# PAGE2-SFP_CONNECTORS.net
KiCad netlist of a schematic drawn in Altium Designer
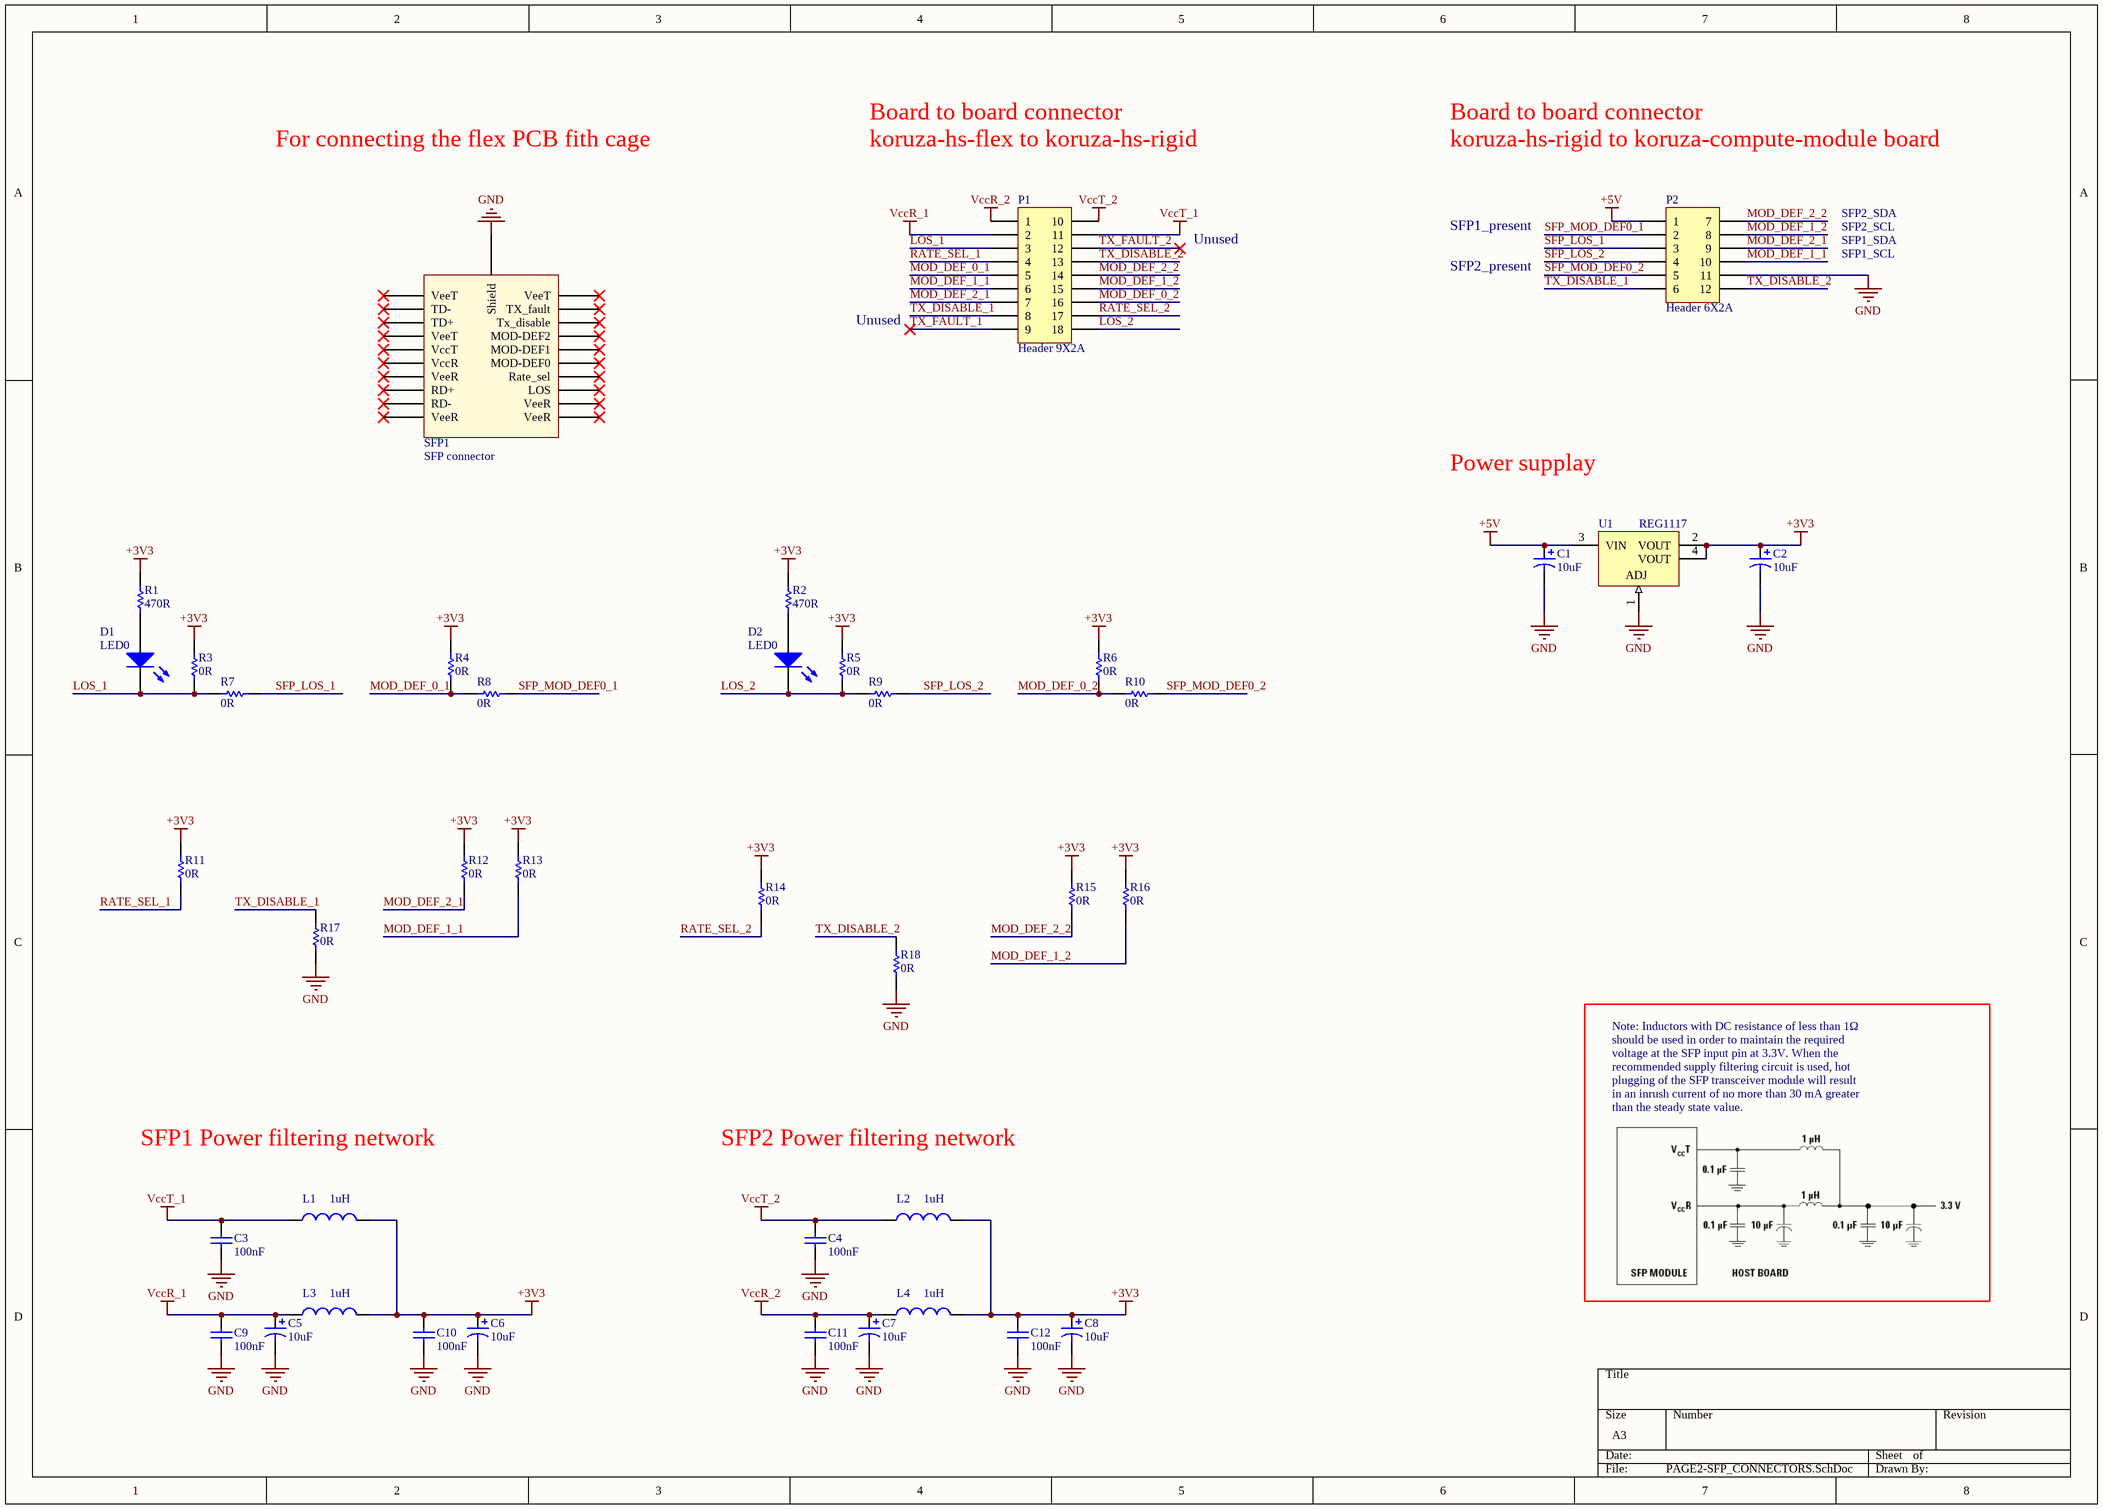
[diagram p0: PAGE2-SFP_CONNECTORS.SchDoc]

(export (version "E")
  (design (tool "Eeschema 10.0.6"))
  (components
    (comp (ref "C1")
      (value "10uF")
      (footprint "CAP0805")
      (description "Polarized Capacitor (Radial)")
      (fields (field (name "PUBLISHER") "Altium Limited"))
      (libsource (lib "PcvLib") (part "CAP0805"))
    )
    (comp (ref "C2")
      (value "10uF")
      (footprint "CAP0805")
      (description "Polarized Capacitor (Radial)")
      (fields (field (name "PUBLISHER") "Altium Limited"))
      (libsource (lib "PcvLib") (part "CAP0805"))
    )
    (comp (ref "C3")
      (value "100nF")
      (footprint "CAP0603")
      (description "Capacitor")
      (fields (field (name "PUBLISHER") "Altium Limited"))
      (libsource (lib "Miscellaneous Devices") (part "Cap"))
    )
    (comp (ref "C4")
      (value "100nF")
      (footprint "CAP0603")
      (description "Capacitor")
      (fields (field (name "PUBLISHER") "Altium Limited"))
      (libsource (lib "Miscellaneous Devices") (part "Cap"))
    )
    (comp (ref "C5")
      (value "10uF")
      (footprint "CAP0805")
      (description "Polarized Capacitor (Radial)")
      (fields (field (name "PUBLISHER") "Altium Limited"))
      (libsource (lib "PcvLib") (part "0805_CAP"))
    )
    (comp (ref "C6")
      (value "10uF")
      (footprint "CAP0805")
      (description "Polarized Capacitor (Radial)")
      (fields (field (name "PUBLISHER") "Altium Limited"))
      (libsource (lib "PcvLib") (part "CAP0805"))
    )
    (comp (ref "C7")
      (value "10uF")
      (footprint "CAP0805")
      (description "Polarized Capacitor (Radial)")
      (fields (field (name "PUBLISHER") "Altium Limited"))
      (libsource (lib "PcvLib") (part "CAP0805"))
    )
    (comp (ref "C8")
      (value "10uF")
      (footprint "CAP0805")
      (description "Polarized Capacitor (Radial)")
      (fields (field (name "PUBLISHER") "Altium Limited"))
      (libsource (lib "PcvLib") (part "CAP0805"))
    )
    (comp (ref "C9")
      (value "100nF")
      (footprint "CAP0603")
      (description "Capacitor")
      (fields (field (name "PUBLISHER") "Altium Limited"))
      (libsource (lib "altium-import") (part "root_1_Cap_"))
    )
    (comp (ref "C10")
      (value "100nF")
      (footprint "CAP0603")
      (description "Capacitor")
      (fields (field (name "PUBLISHER") "Altium Limited"))
      (libsource (lib "altium-import") (part "root_1_Cap_"))
    )
    (comp (ref "C11")
      (value "100nF")
      (footprint "CAP0603")
      (description "Capacitor")
      (fields (field (name "PUBLISHER") "Altium Limited"))
      (libsource (lib "altium-import") (part "root_1_Cap_"))
    )
    (comp (ref "C12")
      (value "100nF")
      (footprint "CAP0603")
      (description "Capacitor")
      (fields (field (name "PUBLISHER") "Altium Limited"))
      (libsource (lib "altium-import") (part "root_1_Cap_"))
    )
    (comp (ref "D1")
      (value "LED0")
      (footprint "DIODE0603")
      (description "Typical INFRARED GaAs LED")
      (fields (field (name "PUBLISHER") "Altium Limited"))
      (libsource (lib "Miscellaneous Devices") (part "LED0"))
    )
    (comp (ref "D2")
      (value "LED0")
      (footprint "DIODE0603")
      (description "Typical INFRARED GaAs LED")
      (fields (field (name "PUBLISHER") "Altium Limited"))
      (libsource (lib "Miscellaneous Devices") (part "LED0"))
    )
    (comp (ref "L1")
      (value "1uH")
      (footprint "6-0805_N")
      (description "Inductor")
      (fields (field (name "PUBLISHER") "Altium Limited"))
      (libsource (lib "Miscellaneous Devices") (part "Inductor"))
    )
    (comp (ref "L2")
      (value "1uH")
      (footprint "6-0805_N")
      (description "Inductor")
      (fields (field (name "PUBLISHER") "Altium Limited"))
      (libsource (lib "Miscellaneous Devices") (part "Inductor"))
    )
    (comp (ref "L3")
      (value "1uH")
      (footprint "6-0805_N")
      (description "Inductor")
      (fields (field (name "PUBLISHER") "Altium Limited"))
      (libsource (lib "Miscellaneous Devices") (part "Inductor"))
    )
    (comp (ref "L4")
      (value "1uH")
      (footprint "6-0805_N")
      (description "Inductor")
      (fields (field (name "PUBLISHER") "Altium Limited"))
      (libsource (lib "Miscellaneous Devices") (part "Inductor"))
    )
    (comp (ref "P1")
      (value "Header 9X2A")
      (footprint "HDR2X9_CEN")
      (description "Header, 9-Pin, Dual row")
      (fields (field (name "PUBLISHER") "Altium Limited"))
      (libsource (lib "Miscellaneous Connectors") (part "Header 9X2A"))
    )
    (comp (ref "P2")
      (value "Header 6X2A")
      (footprint "HDR2X6_CEN")
      (description "Header, 6-Pin, Dual row")
      (fields (field (name "PUBLISHER") "Altium Limited"))
      (libsource (lib "Miscellaneous Connectors") (part "Header 6X2A"))
    )
    (comp (ref "R1")
      (value "470R")
      (footprint "RES0603")
      (description "Resistor")
      (fields (field (name "PUBLISHER") "Altium Limited"))
      (libsource (lib "Miscellaneous Devices") (part "Res1"))
    )
    (comp (ref "R2")
      (value "470R")
      (footprint "RES0603")
      (description "Resistor")
      (fields (field (name "PUBLISHER") "Altium Limited"))
      (libsource (lib "Miscellaneous Devices") (part "Res1"))
    )
    (comp (ref "R3")
      (value "0R")
      (footprint "RES0603")
      (description "Resistor")
      (fields (field (name "PUBLISHER") "Altium Limited"))
      (libsource (lib "Miscellaneous Devices") (part "Res1"))
    )
    (comp (ref "R4")
      (value "0R")
      (footprint "RES0603")
      (description "Resistor")
      (fields (field (name "PUBLISHER") "Altium Limited"))
      (libsource (lib "Miscellaneous Devices") (part "Res1"))
    )
    (comp (ref "R5")
      (value "0R")
      (footprint "RES0603")
      (description "Resistor")
      (fields (field (name "PUBLISHER") "Altium Limited"))
      (libsource (lib "Miscellaneous Devices") (part "Res1"))
    )
    (comp (ref "R6")
      (value "0R")
      (footprint "RES0603")
      (description "Resistor")
      (fields (field (name "PUBLISHER") "Altium Limited"))
      (libsource (lib "Miscellaneous Devices") (part "Res1"))
    )
    (comp (ref "R7")
      (value "0R")
      (footprint "RES0603")
      (description "Resistor")
      (fields (field (name "PUBLISHER") "Altium Limited"))
      (libsource (lib "Miscellaneous Devices") (part "Res1"))
    )
    (comp (ref "R8")
      (value "0R")
      (footprint "RES0603")
      (description "Resistor")
      (fields (field (name "PUBLISHER") "Altium Limited"))
      (libsource (lib "Miscellaneous Devices") (part "Res1"))
    )
    (comp (ref "R9")
      (value "0R")
      (footprint "RES0603")
      (description "Resistor")
      (fields (field (name "PUBLISHER") "Altium Limited"))
      (libsource (lib "Miscellaneous Devices") (part "Res1"))
    )
    (comp (ref "R10")
      (value "0R")
      (footprint "RES0603")
      (description "Resistor")
      (fields (field (name "PUBLISHER") "Altium Limited"))
      (libsource (lib "Miscellaneous Devices") (part "Res1"))
    )
    (comp (ref "R11")
      (value "0R")
      (footprint "RES0603")
      (description "Resistor")
      (fields (field (name "PUBLISHER") "Altium Limited"))
      (libsource (lib "Miscellaneous Devices") (part "Res1"))
    )
    (comp (ref "R12")
      (value "0R")
      (footprint "RES0603")
      (description "Resistor")
      (fields (field (name "PUBLISHER") "Altium Limited"))
      (libsource (lib "Miscellaneous Devices") (part "Res1"))
    )
    (comp (ref "R13")
      (value "0R")
      (footprint "RES0603")
      (description "Resistor")
      (fields (field (name "PUBLISHER") "Altium Limited"))
      (libsource (lib "Miscellaneous Devices") (part "Res1"))
    )
    (comp (ref "R14")
      (value "0R")
      (footprint "RES0603")
      (description "Resistor")
      (fields (field (name "PUBLISHER") "Altium Limited"))
      (libsource (lib "Miscellaneous Devices") (part "Res1"))
    )
    (comp (ref "R15")
      (value "0R")
      (footprint "RES0603")
      (description "Resistor")
      (fields (field (name "PUBLISHER") "Altium Limited"))
      (libsource (lib "Miscellaneous Devices") (part "Res1"))
    )
    (comp (ref "R16")
      (value "0R")
      (footprint "RES0603")
      (description "Resistor")
      (fields (field (name "PUBLISHER") "Altium Limited"))
      (libsource (lib "Miscellaneous Devices") (part "Res1"))
    )
    (comp (ref "R17")
      (value "0R")
      (footprint "RES0603")
      (description "Resistor")
      (fields (field (name "PUBLISHER") "Altium Limited"))
      (libsource (lib "Miscellaneous Devices") (part "Res1"))
    )
    (comp (ref "R18")
      (value "0R")
      (footprint "RES0603")
      (description "Resistor")
      (fields (field (name "PUBLISHER") "Altium Limited"))
      (libsource (lib "Miscellaneous Devices") (part "Res1"))
    )
    (comp (ref "SFP1")
      (value "SFP connector")
      (footprint "PCB_SFP_COVER")
      (libsource (lib "SFP_Rigid_PCB_Cover") (part "SFP connector"))
    )
    (comp (ref "U1")
      (value "REG1117")
      (footprint "TI-DCY4_N")
      (fields (field (name "MANUFACTURER") "Texas Instruments"))
      (libsource (lib "TI Power Management Linear Regulator Single Channel LDO (400-7500mA)") (part "REG1117"))
    )
  )
  (nets
    (net (code "1") (name "+3V3") (class "Default")
      (node (ref "C10") (pin "2") (pinfunction "2_2") (pintype "passive"))
      (node (ref "C12") (pin "2") (pinfunction "2_2") (pintype "passive"))
      (node (ref "C2") (pin "1") (pinfunction "1_1") (pintype "passive"))
      (node (ref "C6") (pin "1") (pinfunction "1_1") (pintype "passive"))
      (node (ref "C8") (pin "1") (pinfunction "1_1") (pintype "passive"))
      (node (ref "L1") (pin "2") (pinfunction "2_2") (pintype "passive"))
      (node (ref "L2") (pin "2") (pinfunction "2_2") (pintype "passive"))
      (node (ref "L3") (pin "2") (pinfunction "2_2") (pintype "passive"))
      (node (ref "L4") (pin "2") (pinfunction "2_2") (pintype "passive"))
      (node (ref "R1") (pin "2") (pinfunction "2_2") (pintype "passive"))
      (node (ref "R11") (pin "1") (pinfunction "1_1") (pintype "passive"))
      (node (ref "R12") (pin "1") (pinfunction "1_1") (pintype "passive"))
      (node (ref "R13") (pin "1") (pinfunction "1_1") (pintype "passive"))
      (node (ref "R14") (pin "1") (pinfunction "1_1") (pintype "passive"))
      (node (ref "R15") (pin "1") (pinfunction "1_1") (pintype "passive"))
      (node (ref "R16") (pin "1") (pinfunction "1_1") (pintype "passive"))
      (node (ref "R2") (pin "2") (pinfunction "2_2") (pintype "passive"))
      (node (ref "R3") (pin "1") (pinfunction "1_1") (pintype "passive"))
      (node (ref "R4") (pin "1") (pinfunction "1_1") (pintype "passive"))
      (node (ref "R5") (pin "1") (pinfunction "1_1") (pintype "passive"))
      (node (ref "R6") (pin "1") (pinfunction "1_1") (pintype "passive"))
      (node (ref "U1") (pin "2") (pinfunction "VOUT_2") (pintype "power_in"))
      (node (ref "U1") (pin "4") (pinfunction "VOUT_4") (pintype "power_in"))
    )
    (net (code "2") (name "+5V") (class "Default")
      (node (ref "C1") (pin "1") (pinfunction "1_1") (pintype "passive"))
      (node (ref "P2") (pin "1") (pinfunction "1_1") (pintype "passive"))
      (node (ref "U1") (pin "3") (pinfunction "VIN_3") (pintype "power_in"))
    )
    (net (code "3") (name "/LOS_1") (class "Default")
      (node (ref "D1") (pin "2") (pinfunction "K_2") (pintype "passive"))
      (node (ref "P1") (pin "3") (pinfunction "3_3") (pintype "passive"))
      (node (ref "R3") (pin "2") (pinfunction "2_2") (pintype "passive"))
      (node (ref "R7") (pin "1") (pinfunction "1_1") (pintype "passive"))
    )
    (net (code "4") (name "/LOS_2") (class "Default")
      (node (ref "D2") (pin "2") (pinfunction "K_2") (pintype "passive"))
      (node (ref "P1") (pin "18") (pinfunction "18_18") (pintype "passive"))
      (node (ref "R5") (pin "2") (pinfunction "2_2") (pintype "passive"))
      (node (ref "R9") (pin "1") (pinfunction "1_1") (pintype "passive"))
    )
    (net (code "5") (name "/MOD_DEF_0_1") (class "Default")
      (node (ref "P1") (pin "5") (pinfunction "5_5") (pintype "passive"))
      (node (ref "R4") (pin "2") (pinfunction "2_2") (pintype "passive"))
      (node (ref "R8") (pin "1") (pinfunction "1_1") (pintype "passive"))
    )
    (net (code "6") (name "/MOD_DEF_0_2") (class "Default")
      (node (ref "P1") (pin "16") (pinfunction "16_16") (pintype "passive"))
      (node (ref "R10") (pin "1") (pinfunction "1_1") (pintype "passive"))
      (node (ref "R6") (pin "2") (pinfunction "2_2") (pintype "passive"))
    )
    (net (code "7") (name "/MOD_DEF_1_1") (class "Default")
      (node (ref "P1") (pin "6") (pinfunction "6_6") (pintype "passive"))
      (node (ref "P2") (pin "10") (pinfunction "10_10") (pintype "passive"))
      (node (ref "R13") (pin "2") (pinfunction "2_2") (pintype "passive"))
    )
    (net (code "8") (name "/MOD_DEF_1_2") (class "Default")
      (node (ref "P1") (pin "15") (pinfunction "15_15") (pintype "passive"))
      (node (ref "P2") (pin "8") (pinfunction "8_8") (pintype "passive"))
      (node (ref "R16") (pin "2") (pinfunction "2_2") (pintype "passive"))
    )
    (net (code "9") (name "/MOD_DEF_2_1") (class "Default")
      (node (ref "P1") (pin "7") (pinfunction "7_7") (pintype "passive"))
      (node (ref "P2") (pin "9") (pinfunction "9_9") (pintype "passive"))
      (node (ref "R12") (pin "2") (pinfunction "2_2") (pintype "passive"))
    )
    (net (code "10") (name "/MOD_DEF_2_2") (class "Default")
      (node (ref "P1") (pin "14") (pinfunction "14_14") (pintype "passive"))
      (node (ref "P2") (pin "7") (pinfunction "7_7") (pintype "passive"))
      (node (ref "R15") (pin "2") (pinfunction "2_2") (pintype "passive"))
    )
    (net (code "11") (name "/RATE_SEL_1") (class "Default")
      (node (ref "P1") (pin "4") (pinfunction "4_4") (pintype "passive"))
      (node (ref "R11") (pin "2") (pinfunction "2_2") (pintype "passive"))
    )
    (net (code "12") (name "/RATE_SEL_2") (class "Default")
      (node (ref "P1") (pin "17") (pinfunction "17_17") (pintype "passive"))
      (node (ref "R14") (pin "2") (pinfunction "2_2") (pintype "passive"))
    )
    (net (code "13") (name "/SFP_LOS_1") (class "Default")
      (node (ref "P2") (pin "3") (pinfunction "3_3") (pintype "passive"))
      (node (ref "R7") (pin "2") (pinfunction "2_2") (pintype "passive"))
    )
    (net (code "14") (name "/SFP_LOS_2") (class "Default")
      (node (ref "P2") (pin "4") (pinfunction "4_4") (pintype "passive"))
      (node (ref "R9") (pin "2") (pinfunction "2_2") (pintype "passive"))
    )
    (net (code "15") (name "/SFP_MOD_DEF0_1") (class "Default")
      (node (ref "P2") (pin "2") (pinfunction "2_2") (pintype "passive"))
      (node (ref "R8") (pin "2") (pinfunction "2_2") (pintype "passive"))
    )
    (net (code "16") (name "/SFP_MOD_DEF0_2") (class "Default")
      (node (ref "P2") (pin "5") (pinfunction "5_5") (pintype "passive"))
      (node (ref "R10") (pin "2") (pinfunction "2_2") (pintype "passive"))
    )
    (net (code "17") (name "/TX_DISABLE_1") (class "Default")
      (node (ref "P1") (pin "8") (pinfunction "8_8") (pintype "passive"))
      (node (ref "P2") (pin "6") (pinfunction "6_6") (pintype "passive"))
      (node (ref "R17") (pin "1") (pinfunction "1_1") (pintype "passive"))
    )
    (net (code "18") (name "/TX_DISABLE_2") (class "Default")
      (node (ref "P1") (pin "13") (pinfunction "13_13") (pintype "passive"))
      (node (ref "P2") (pin "12") (pinfunction "12_12") (pintype "passive"))
      (node (ref "R18") (pin "1") (pinfunction "1_1") (pintype "passive"))
    )
    (net (code "19") (name "/TX_FAULT_1") (class "Default")
      (node (ref "P1") (pin "9") (pinfunction "9_9") (pintype "passive+no_connect"))
    )
    (net (code "20") (name "/TX_FAULT_2") (class "Default")
      (node (ref "P1") (pin "12") (pinfunction "12_12") (pintype "passive+no_connect"))
    )
    (net (code "21") (name "GND") (class "Default")
      (node (ref "C1") (pin "2") (pinfunction "2_2") (pintype "passive"))
      (node (ref "C10") (pin "1") (pinfunction "1_1") (pintype "passive"))
      (node (ref "C11") (pin "1") (pinfunction "1_1") (pintype "passive"))
      (node (ref "C12") (pin "1") (pinfunction "1_1") (pintype "passive"))
      (node (ref "C2") (pin "2") (pinfunction "2_2") (pintype "passive"))
      (node (ref "C3") (pin "1") (pinfunction "1_1") (pintype "passive"))
      (node (ref "C4") (pin "1") (pinfunction "1_1") (pintype "passive"))
      (node (ref "C5") (pin "2") (pinfunction "2_2") (pintype "passive"))
      (node (ref "C6") (pin "2") (pinfunction "2_2") (pintype "passive"))
      (node (ref "C7") (pin "2") (pinfunction "2_2") (pintype "passive"))
      (node (ref "C8") (pin "2") (pinfunction "2_2") (pintype "passive"))
      (node (ref "C9") (pin "1") (pinfunction "1_1") (pintype "passive"))
      (node (ref "P2") (pin "11") (pinfunction "11_11") (pintype "passive"))
      (node (ref "R17") (pin "2") (pinfunction "2_2") (pintype "passive"))
      (node (ref "R18") (pin "2") (pinfunction "2_2") (pintype "passive"))
      (node (ref "SFP1") (pin "21") (pinfunction "Shield_21") (pintype "power_in"))
      (node (ref "U1") (pin "1") (pinfunction "ADJ_1") (pintype "input"))
    )
    (net (code "22") (name "Net-(D1-A)") (class "Default")
      (node (ref "D1") (pin "1") (pinfunction "A_1") (pintype "passive"))
      (node (ref "R1") (pin "1") (pinfunction "1_1") (pintype "passive"))
    )
    (net (code "23") (name "Net-(D2-A)") (class "Default")
      (node (ref "D2") (pin "1") (pinfunction "A_1") (pintype "passive"))
      (node (ref "R2") (pin "1") (pinfunction "1_1") (pintype "passive"))
    )
    (net (code "24") (name "VccR_1") (class "Default")
      (node (ref "C5") (pin "1") (pinfunction "1_1") (pintype "passive"))
      (node (ref "C9") (pin "2") (pinfunction "2_2") (pintype "passive"))
      (node (ref "L3") (pin "1") (pinfunction "1_1") (pintype "passive"))
      (node (ref "P1") (pin "2") (pinfunction "2_2") (pintype "passive"))
    )
    (net (code "25") (name "VccR_2") (class "Default")
      (node (ref "C11") (pin "2") (pinfunction "2_2") (pintype "passive"))
      (node (ref "C7") (pin "1") (pinfunction "1_1") (pintype "passive"))
      (node (ref "L4") (pin "1") (pinfunction "1_1") (pintype "passive"))
      (node (ref "P1") (pin "1") (pinfunction "1_1") (pintype "passive"))
    )
    (net (code "26") (name "VccT_1") (class "Default")
      (node (ref "C3") (pin "2") (pinfunction "2_2") (pintype "passive"))
      (node (ref "L1") (pin "1") (pinfunction "1_1") (pintype "passive"))
      (node (ref "P1") (pin "11") (pinfunction "11_11") (pintype "passive"))
    )
    (net (code "27") (name "VccT_2") (class "Default")
      (node (ref "C4") (pin "2") (pinfunction "2_2") (pintype "passive"))
      (node (ref "L2") (pin "1") (pinfunction "1_1") (pintype "passive"))
      (node (ref "P1") (pin "10") (pinfunction "10_10") (pintype "passive"))
    )
    (net (code "28") (name "unconnected-(SFP1-LOS-Pad8)") (class "Default")
      (node (ref "SFP1") (pin "8") (pinfunction "LOS_8") (pintype "power_in+no_connect"))
    )
    (net (code "29") (name "unconnected-(SFP1-MOD-DEF0-Pad6)") (class "Default")
      (node (ref "SFP1") (pin "6") (pinfunction "MOD-DEF0_6") (pintype "power_in+no_connect"))
    )
    (net (code "30") (name "unconnected-(SFP1-MOD-DEF1-Pad5)") (class "Default")
      (node (ref "SFP1") (pin "5") (pinfunction "MOD-DEF1_5") (pintype "power_in+no_connect"))
    )
    (net (code "31") (name "unconnected-(SFP1-MOD-DEF2-Pad4)") (class "Default")
      (node (ref "SFP1") (pin "4") (pinfunction "MOD-DEF2_4") (pintype "power_in+no_connect"))
    )
    (net (code "32") (name "unconnected-(SFP1-RD+-Pad13)") (class "Default")
      (node (ref "SFP1") (pin "13") (pinfunction "RD+_13") (pintype "power_in+no_connect"))
    )
    (net (code "33") (name "unconnected-(SFP1-RD--Pad12)") (class "Default")
      (node (ref "SFP1") (pin "12") (pinfunction "RD-_12") (pintype "power_in+no_connect"))
    )
    (net (code "34") (name "unconnected-(SFP1-Rate_sel-Pad7)") (class "Default")
      (node (ref "SFP1") (pin "7") (pinfunction "Rate_sel_7") (pintype "power_in+no_connect"))
    )
    (net (code "35") (name "unconnected-(SFP1-TD+-Pad18)") (class "Default")
      (node (ref "SFP1") (pin "18") (pinfunction "TD+_18") (pintype "power_in+no_connect"))
    )
    (net (code "36") (name "unconnected-(SFP1-TD--Pad19)") (class "Default")
      (node (ref "SFP1") (pin "19") (pinfunction "TD-_19") (pintype "power_in+no_connect"))
    )
    (net (code "37") (name "unconnected-(SFP1-TX_fault-Pad2)") (class "Default")
      (node (ref "SFP1") (pin "2") (pinfunction "TX_fault_2") (pintype "power_in+no_connect"))
    )
    (net (code "38") (name "unconnected-(SFP1-Tx_disable-Pad3)") (class "Default")
      (node (ref "SFP1") (pin "3") (pinfunction "Tx_disable_3") (pintype "power_in+no_connect"))
    )
    (net (code "39") (name "unconnected-(SFP1-VccR-Pad15)") (class "Default")
      (node (ref "SFP1") (pin "15") (pinfunction "VccR_15") (pintype "power_in+no_connect"))
    )
    (net (code "40") (name "unconnected-(SFP1-VccT-Pad16)") (class "Default")
      (node (ref "SFP1") (pin "16") (pinfunction "VccT_16") (pintype "power_in+no_connect"))
    )
    (net (code "41") (name "unconnected-(SFP1-VeeR-Pad9)") (class "Default")
      (node (ref "SFP1") (pin "9") (pinfunction "VeeR_9") (pintype "power_in+no_connect"))
    )
    (net (code "42") (name "unconnected-(SFP1-VeeR-Pad10)") (class "Default")
      (node (ref "SFP1") (pin "10") (pinfunction "VeeR_10") (pintype "power_in+no_connect"))
    )
    (net (code "43") (name "unconnected-(SFP1-VeeR-Pad11)") (class "Default")
      (node (ref "SFP1") (pin "11") (pinfunction "VeeR_11") (pintype "power_in+no_connect"))
    )
    (net (code "44") (name "unconnected-(SFP1-VeeR-Pad14)") (class "Default")
      (node (ref "SFP1") (pin "14") (pinfunction "VeeR_14") (pintype "power_in+no_connect"))
    )
    (net (code "45") (name "unconnected-(SFP1-VeeT-Pad1)") (class "Default")
      (node (ref "SFP1") (pin "1") (pinfunction "VeeT_1") (pintype "power_in+no_connect"))
    )
    (net (code "46") (name "unconnected-(SFP1-VeeT-Pad17)") (class "Default")
      (node (ref "SFP1") (pin "17") (pinfunction "VeeT_17") (pintype "power_in+no_connect"))
    )
    (net (code "47") (name "unconnected-(SFP1-VeeT-Pad20)") (class "Default")
      (node (ref "SFP1") (pin "20") (pinfunction "VeeT_20") (pintype "power_in+no_connect"))
    )
  )
)
